# main.net
KiCad netlist of a schematic drawn in EAGLE
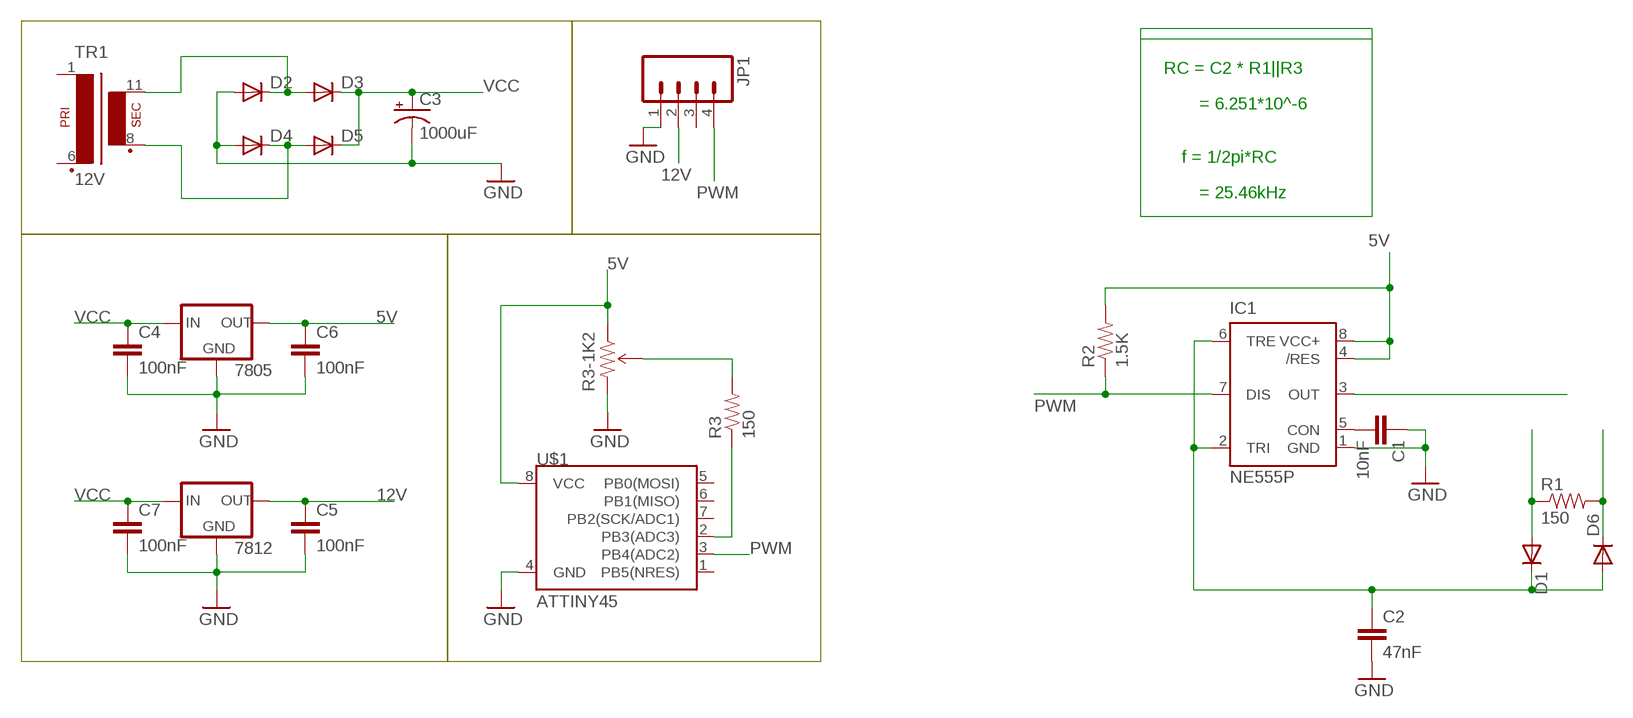
[diagram p0: schematic, sheet 1]

(export (version "E")
  (design (tool "Eeschema 10.0.6"))
  (components
    (comp (ref "7805")
      (value "V_REG_78XX-TO-220")
      (footprint "eagle-import:TO-220-ALT")
      (libsource (lib "eagle-import") (part "V_REG_78XX-TO-220"))
    )
    (comp (ref "7812")
      (value "V_REG_78XX-TO-220")
      (footprint "eagle-import:TO-220-ALT")
      (libsource (lib "eagle-import") (part "V_REG_78XX-TO-220"))
    )
    (comp (ref "C1")
      (value "10nF")
      (footprint "eagle-import:CAP-PTH-5MM")
      (libsource (lib "eagle-import") (part "CAPPTH1"))
    )
    (comp (ref "C2")
      (value "47nF")
      (footprint "eagle-import:CAP-PTH-5MM")
      (libsource (lib "eagle-import") (part "CAPPTH1"))
    )
    (comp (ref "C3")
      (value "1000uF")
      (footprint "eagle-import:CPOL-RADIAL-100UF-25V")
      (libsource (lib "eagle-import") (part "CAP_POLPTH1"))
    )
    (comp (ref "C4")
      (value "100nF")
      (footprint "eagle-import:CAP-PTH-SMALL")
      (libsource (lib "eagle-import") (part "CAPPTH"))
    )
    (comp (ref "C5")
      (value "100nF")
      (footprint "eagle-import:CAP-PTH-SMALL")
      (libsource (lib "eagle-import") (part "CAPPTH"))
    )
    (comp (ref "C6")
      (value "100nF")
      (footprint "eagle-import:CAP-PTH-SMALL")
      (libsource (lib "eagle-import") (part "CAPPTH"))
    )
    (comp (ref "C7")
      (value "100nF")
      (footprint "eagle-import:CAP-PTH-SMALL")
      (libsource (lib "eagle-import") (part "CAPPTH"))
    )
    (comp (ref "D1")
      (value "DIODE1N4148")
      (footprint "eagle-import:DIODE-1N4148")
      (libsource (lib "eagle-import") (part "DIODE1N4148"))
    )
    (comp (ref "D2")
      (value "DIODEPTH")
      (footprint "eagle-import:DIODE-1N4001")
      (libsource (lib "eagle-import") (part "DIODEPTH"))
    )
    (comp (ref "D3")
      (value "DIODEPTH")
      (footprint "eagle-import:DIODE-1N4001")
      (libsource (lib "eagle-import") (part "DIODEPTH"))
    )
    (comp (ref "D4")
      (value "DIODEPTH")
      (footprint "eagle-import:DIODE-1N4001")
      (libsource (lib "eagle-import") (part "DIODEPTH"))
    )
    (comp (ref "D5")
      (value "DIODEPTH")
      (footprint "eagle-import:DIODE-1N4001")
      (libsource (lib "eagle-import") (part "DIODEPTH"))
    )
    (comp (ref "D6")
      (value "DIODE1N4148")
      (footprint "eagle-import:DIODE-1N4148")
      (libsource (lib "eagle-import") (part "DIODE1N4148"))
    )
    (comp (ref "IC1")
      (value "NE555P")
      (footprint "eagle-import:DIL-08")
      (fields (field (name "MF") "Arrow Electronics") (field (name "MPN") "NE555N"))
      (libsource (lib "eagle-import") (part "NE555P"))
    )
    (comp (ref "JP1")
      (value "M04POLAR")
      (footprint "eagle-import:MOLEX-1X4")
      (libsource (lib "eagle-import") (part "M04POLAR"))
    )
    (comp (ref "R1")
      (value "150")
      (footprint "eagle-import:AXIAL-0.4")
      (libsource (lib "eagle-import") (part "RESISTORPTH-1/4W"))
    )
    (comp (ref "R2")
      (value "1.5K")
      (footprint "eagle-import:AXIAL-0.4")
      (libsource (lib "eagle-import") (part "RESISTORPTH-1/4W"))
    )
    (comp (ref "R3")
      (value "150")
      (footprint "eagle-import:AXIAL-0.4")
      (libsource (lib "eagle-import") (part "RESISTORPTH-1/4W"))
    )
    (comp (ref "R3-1K2")
      (value "TRIMPOTPTH")
      (footprint "eagle-import:TRIM_POT_PTH")
      (libsource (lib "eagle-import") (part "TRIMPOTPTH"))
    )
    (comp (ref "TR1")
      (value "12V")
      (footprint "eagle-import:EI48-1")
      (libsource (lib "eagle-import") (part "EI48-1"))
    )
    (comp (ref "U$1")
      (value "ATTINY45")
      (footprint "eagle-import:SO08-EIAJ")
      (libsource (lib "eagle-import") (part "ATTINY45"))
    )
  )
  (nets
    (net (code "1") (name "/5V") (class "Default")
      (node (ref "7805") (pin "OUT") (pinfunction "OUT_OUT") (pintype "output"))
      (node (ref "C6") (pin "1") (pinfunction "1_1") (pintype "passive"))
      (node (ref "IC1") (pin "4") (pinfunction "/RES_4") (pintype "input"))
      (node (ref "IC1") (pin "8") (pinfunction "VCC+_8") (pintype "power_in"))
      (node (ref "R2") (pin "P$2") (pinfunction "2_P$2") (pintype "passive"))
      (node (ref "R3-1K2") (pin "1") (pinfunction "CCW_1") (pintype "passive"))
      (node (ref "U$1") (pin "8") (pinfunction "VCC_8") (pintype "bidirectional"))
    )
    (net (code "2") (name "/12V") (class "Default")
      (node (ref "7812") (pin "OUT") (pinfunction "OUT_OUT") (pintype "output"))
      (node (ref "C5") (pin "1") (pinfunction "1_1") (pintype "passive"))
      (node (ref "JP1") (pin "2") (pinfunction "2_2") (pintype "passive"))
    )
    (net (code "3") (name "/PWM") (class "Default")
      (node (ref "IC1") (pin "7") (pinfunction "DIS_7") (pintype "input"))
      (node (ref "JP1") (pin "4") (pinfunction "4_4") (pintype "passive"))
      (node (ref "R2") (pin "P$1") (pinfunction "1_P$1") (pintype "passive"))
      (node (ref "U$1") (pin "3") (pinfunction "PB4(ADC2)_3") (pintype "bidirectional"))
    )
    (net (code "4") (name "/VCC") (class "Default")
      (node (ref "7805") (pin "IN") (pinfunction "IN_IN") (pintype "input"))
      (node (ref "7812") (pin "IN") (pinfunction "IN_IN") (pintype "input"))
      (node (ref "C3") (pin "1") (pinfunction "+_1") (pintype "passive"))
      (node (ref "C4") (pin "1") (pinfunction "1_1") (pintype "passive"))
      (node (ref "C7") (pin "1") (pinfunction "1_1") (pintype "passive"))
      (node (ref "D3") (pin "C") (pinfunction "C_C") (pintype "passive"))
      (node (ref "D5") (pin "C") (pinfunction "C_C") (pintype "passive"))
    )
    (net (code "5") (name "GND") (class "Default")
      (node (ref "7805") (pin "GND") (pinfunction "GND_GND") (pintype "input"))
      (node (ref "7812") (pin "GND") (pinfunction "GND_GND") (pintype "input"))
      (node (ref "C1") (pin "1") (pinfunction "1_1") (pintype "passive"))
      (node (ref "C2") (pin "2") (pinfunction "2_2") (pintype "passive"))
      (node (ref "C3") (pin "2") (pinfunction "-_2") (pintype "passive"))
      (node (ref "C4") (pin "2") (pinfunction "2_2") (pintype "passive"))
      (node (ref "C5") (pin "2") (pinfunction "2_2") (pintype "passive"))
      (node (ref "C6") (pin "2") (pinfunction "2_2") (pintype "passive"))
      (node (ref "C7") (pin "2") (pinfunction "2_2") (pintype "passive"))
      (node (ref "D2") (pin "A") (pinfunction "A_A") (pintype "passive"))
      (node (ref "D4") (pin "A") (pinfunction "A_A") (pintype "passive"))
      (node (ref "IC1") (pin "1") (pinfunction "GND_1") (pintype "power_in"))
      (node (ref "JP1") (pin "1") (pinfunction "1_1") (pintype "passive"))
      (node (ref "R3-1K2") (pin "3") (pinfunction "CW_3") (pintype "passive"))
      (node (ref "U$1") (pin "4") (pinfunction "GND_4") (pintype "bidirectional"))
    )
    (net (code "6") (name "Net-(IC1-CON)") (class "Default")
      (node (ref "C1") (pin "2") (pinfunction "2_2") (pintype "passive"))
      (node (ref "IC1") (pin "5") (pinfunction "CON_5") (pintype "input"))
    )
    (net (code "7") (name "Net-(IC1-TRE)") (class "Default")
      (node (ref "C2") (pin "1") (pinfunction "1_1") (pintype "passive"))
      (node (ref "D1") (pin "C") (pinfunction "C_C") (pintype "passive"))
      (node (ref "D6") (pin "A") (pinfunction "A_A") (pintype "passive"))
      (node (ref "IC1") (pin "2") (pinfunction "TRI_2") (pintype "input"))
      (node (ref "IC1") (pin "6") (pinfunction "TRE_6") (pintype "input"))
    )
    (net (code "8") (name "Net-(R1-1)") (class "Default")
      (node (ref "D1") (pin "A") (pinfunction "A_A") (pintype "passive"))
      (node (ref "R1") (pin "P$1") (pinfunction "1_P$1") (pintype "passive"))
    )
    (net (code "9") (name "Net-(R1-2)") (class "Default")
      (node (ref "D6") (pin "C") (pinfunction "C_C") (pintype "passive"))
      (node (ref "R1") (pin "P$2") (pinfunction "2_P$2") (pintype "passive"))
    )
    (net (code "10") (name "Net-(R3-1)") (class "Default")
      (node (ref "R3") (pin "P$1") (pinfunction "1_P$1") (pintype "passive"))
      (node (ref "U$1") (pin "2") (pinfunction "PB3(ADC3)_2") (pintype "bidirectional"))
    )
    (net (code "11") (name "Net-(R3-1K2-WIPER)") (class "Default")
      (node (ref "R3") (pin "P$2") (pinfunction "2_P$2") (pintype "passive"))
      (node (ref "R3-1K2") (pin "2") (pinfunction "WIPER_2") (pintype "passive"))
    )
    (net (code "12") (name "Net-(TR1-S3)") (class "Default")
      (node (ref "D4") (pin "C") (pinfunction "C_C") (pintype "passive"))
      (node (ref "D5") (pin "A") (pinfunction "A_A") (pintype "passive"))
      (node (ref "TR1") (pin "8") (pinfunction "S3_8") (pintype "passive"))
    )
    (net (code "13") (name "Net-(TR1-S4)") (class "Default")
      (node (ref "D2") (pin "C") (pinfunction "C_C") (pintype "passive"))
      (node (ref "D3") (pin "A") (pinfunction "A_A") (pintype "passive"))
      (node (ref "TR1") (pin "11") (pinfunction "S4_11") (pintype "passive"))
    )
    (net (code "14") (name "unconnected-(IC1-OUT-Pad3)") (class "Default")
      (node (ref "IC1") (pin "3") (pinfunction "OUT_3") (pintype "output"))
    )
    (net (code "15") (name "unconnected-(JP1-Pad3)") (class "Default")
      (node (ref "JP1") (pin "3") (pinfunction "3_3") (pintype "passive"))
    )
    (net (code "16") (name "unconnected-(TR1-P1-Pad1)") (class "Default")
      (node (ref "TR1") (pin "1") (pinfunction "P1_1") (pintype "passive"))
    )
    (net (code "17") (name "unconnected-(TR1-P2-Pad6)") (class "Default")
      (node (ref "TR1") (pin "6") (pinfunction "P2_6") (pintype "passive"))
    )
    (net (code "18") (name "unconnected-(U$1-PB0(MOSI)-Pad5)") (class "Default")
      (node (ref "U$1") (pin "5") (pinfunction "PB0(MOSI)_5") (pintype "bidirectional"))
    )
    (net (code "19") (name "unconnected-(U$1-PB1(MISO)-Pad6)") (class "Default")
      (node (ref "U$1") (pin "6") (pinfunction "PB1(MISO)_6") (pintype "bidirectional"))
    )
    (net (code "20") (name "unconnected-(U$1-PB2(SCK{slash}ADC1)-Pad7)") (class "Default")
      (node (ref "U$1") (pin "7") (pinfunction "PB2(SCK/ADC1)_7") (pintype "bidirectional"))
    )
    (net (code "21") (name "unconnected-(U$1-PB5(NRES)-Pad1)") (class "Default")
      (node (ref "U$1") (pin "1") (pinfunction "PB5(NRES)_1") (pintype "bidirectional"))
    )
  )
)
